# KMO_IO_M.net
KiCad netlist of a schematic drawn in EAGLE
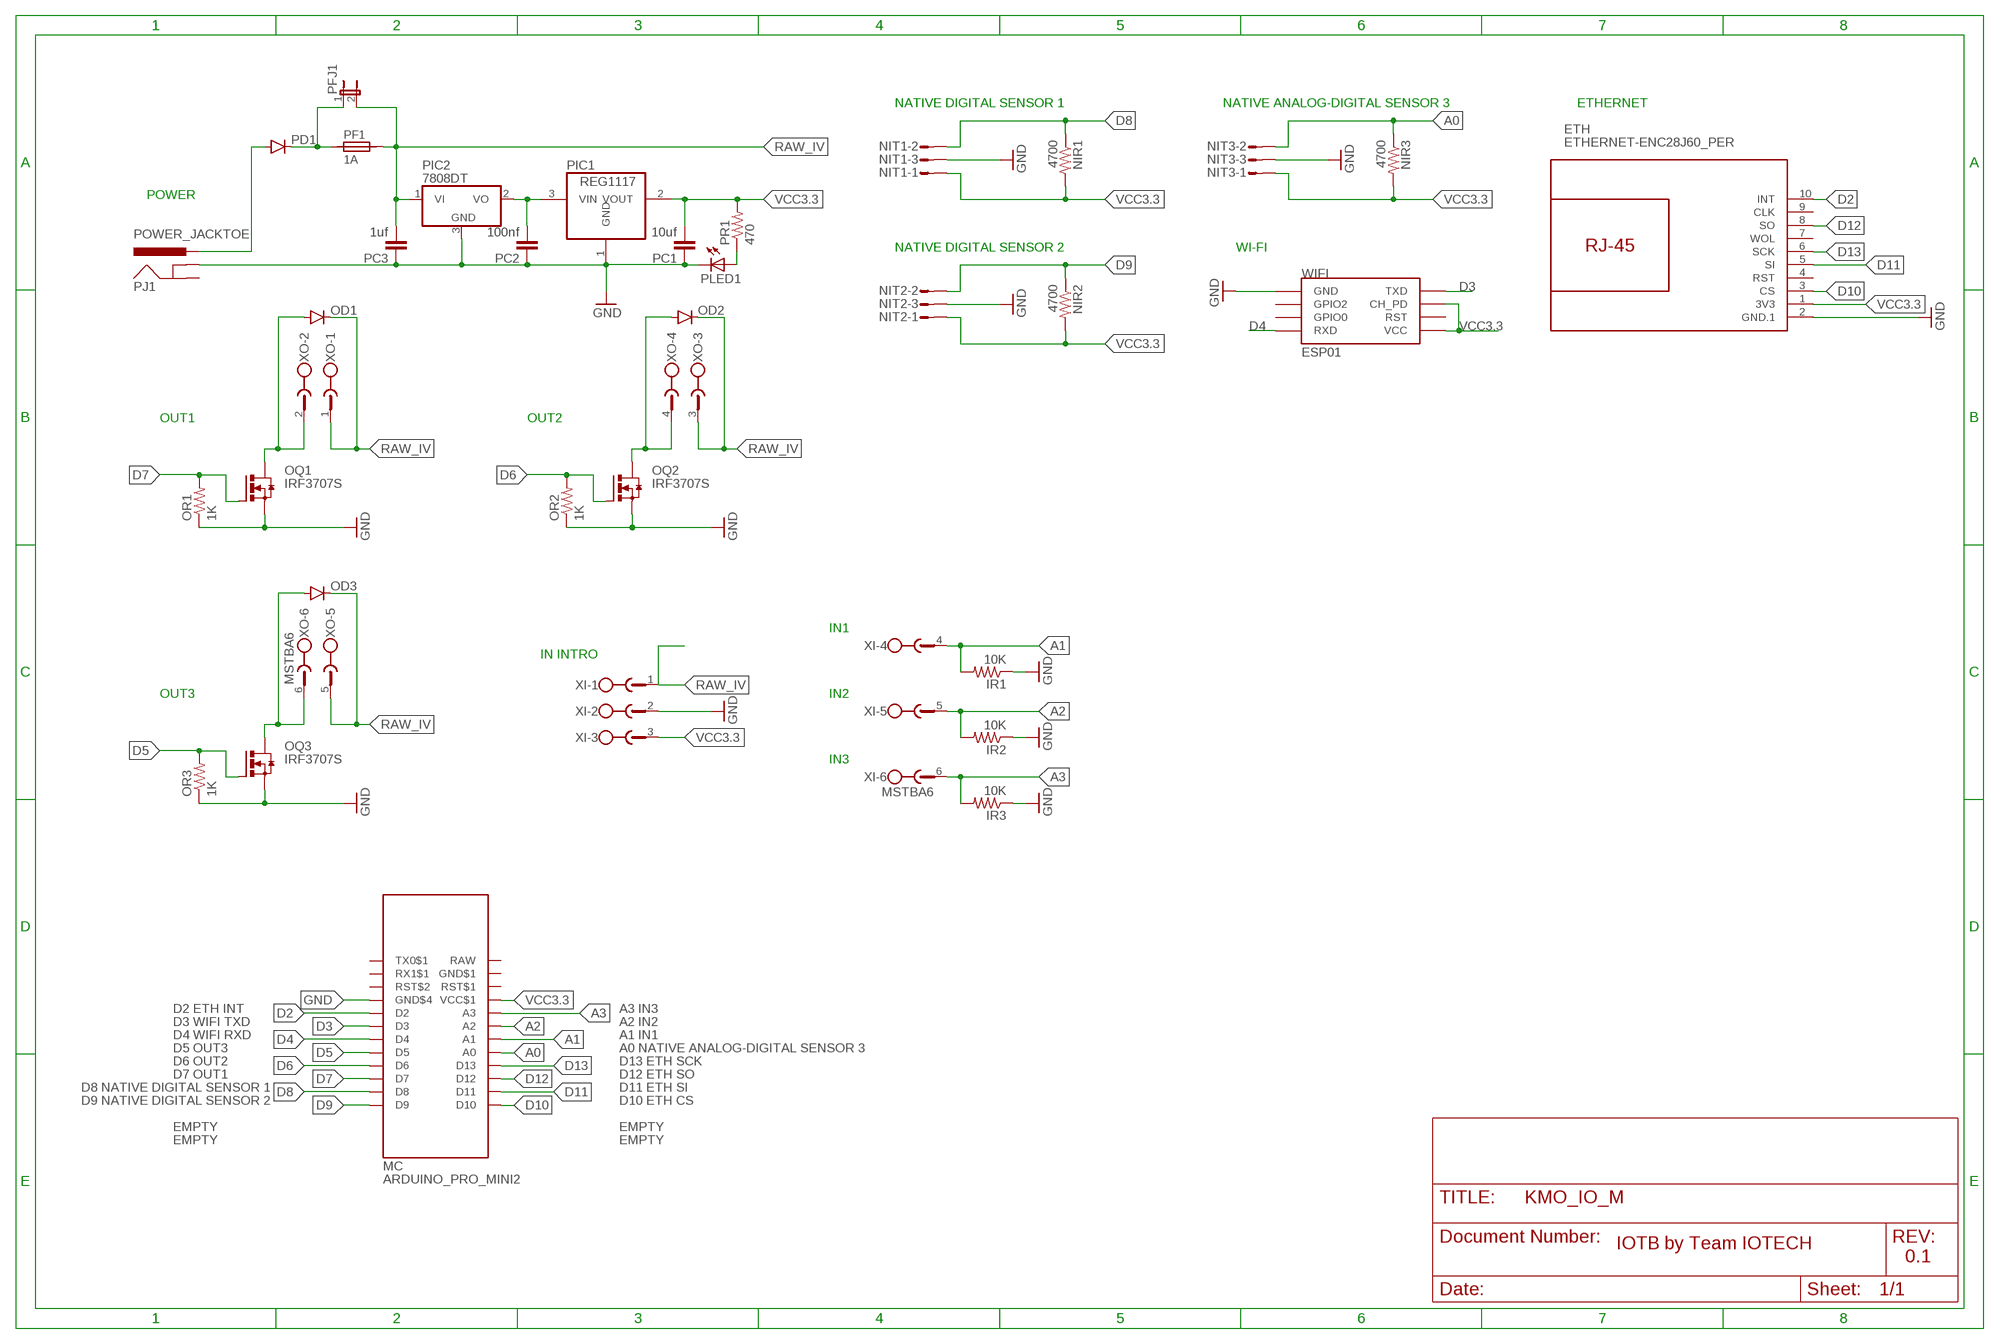
[diagram p0: schematic, sheet 1]

(export (version "E")
  (design (tool "Eeschema 10.0.6"))
  (components
    (comp (ref "ETH")
      (value "ETHERNET-ENC28J60_PER")
      (footprint "eagle-import:ETHERNET-ENC28J60_PER")
      (libsource (lib "eagle-import") (part "ETHERNET-ENC28J60_PER"))
    )
    (comp (ref "IR1")
      (value "10K")
      (footprint "eagle-import:0805")
      (libsource (lib "eagle-import") (part "RESISTOR0805-RES"))
    )
    (comp (ref "IR2")
      (value "10K")
      (footprint "eagle-import:0805")
      (libsource (lib "eagle-import") (part "RESISTOR0805-RES"))
    )
    (comp (ref "IR3")
      (value "10K")
      (footprint "eagle-import:0805")
      (libsource (lib "eagle-import") (part "RESISTOR0805-RES"))
    )
    (comp (ref "MC")
      (value "ARDUINO_PRO_MINI2")
      (footprint "eagle-import:ARDUINO_PRO_MINI2")
      (libsource (lib "eagle-import") (part "ARDUINO_PRO_MINI2"))
    )
    (comp (ref "NIR1")
      (value "4700")
      (footprint "eagle-import:0805")
      (libsource (lib "eagle-import") (part "RESISTOR0805-RES"))
    )
    (comp (ref "NIR2")
      (value "4700")
      (footprint "eagle-import:0805")
      (libsource (lib "eagle-import") (part "RESISTOR0805-RES"))
    )
    (comp (ref "NIR3")
      (value "4700")
      (footprint "eagle-import:0805")
      (libsource (lib "eagle-import") (part "RESISTOR0805-RES"))
    )
    (comp (ref "NIT1")
      (value "S03P")
      (footprint "eagle-import:S03P")
      (libsource (lib "eagle-import") (part "S03P"))
    )
    (comp (ref "NIT2")
      (value "S03P")
      (footprint "eagle-import:S03P")
      (libsource (lib "eagle-import") (part "S03P"))
    )
    (comp (ref "NIT3")
      (value "S03P")
      (footprint "eagle-import:S03P")
      (libsource (lib "eagle-import") (part "S03P"))
    )
    (comp (ref "OD1")
      (value "DIODESMA")
      (footprint "eagle-import:SMA-DIODE")
      (libsource (lib "eagle-import") (part "DIODESMA"))
    )
    (comp (ref "OD2")
      (value "DIODESMA")
      (footprint "eagle-import:SMA-DIODE")
      (libsource (lib "eagle-import") (part "DIODESMA"))
    )
    (comp (ref "OD3")
      (value "DIODESMA")
      (footprint "eagle-import:SMA-DIODE")
      (libsource (lib "eagle-import") (part "DIODESMA"))
    )
    (comp (ref "OQ1")
      (value "IRF3707S")
      (footprint "eagle-import:D2PACK")
      (libsource (lib "eagle-import") (part "IRF3704S"))
    )
    (comp (ref "OQ2")
      (value "IRF3707S")
      (footprint "eagle-import:D2PACK")
      (libsource (lib "eagle-import") (part "IRF3704S"))
    )
    (comp (ref "OQ3")
      (value "IRF3707S")
      (footprint "eagle-import:D2PACK")
      (libsource (lib "eagle-import") (part "IRF3704S"))
    )
    (comp (ref "OR1")
      (value "1K")
      (footprint "eagle-import:0805")
      (libsource (lib "eagle-import") (part "RESISTOR0805-RES"))
    )
    (comp (ref "OR2")
      (value "1K")
      (footprint "eagle-import:0805")
      (libsource (lib "eagle-import") (part "RESISTOR0805-RES"))
    )
    (comp (ref "OR3")
      (value "1K")
      (footprint "eagle-import:0805")
      (libsource (lib "eagle-import") (part "RESISTOR0805-RES"))
    )
    (comp (ref "PC1")
      (value "10uf")
      (footprint "eagle-import:0805")
      (libsource (lib "eagle-import") (part "CAP0805"))
    )
    (comp (ref "PC2")
      (value "100nf")
      (footprint "eagle-import:0805")
      (libsource (lib "eagle-import") (part "CAP0805"))
    )
    (comp (ref "PC3")
      (value "1uf")
      (footprint "eagle-import:0805")
      (libsource (lib "eagle-import") (part "CAP0805"))
    )
    (comp (ref "PD1")
      (value "DIODESMA")
      (footprint "eagle-import:SMA-DIODE")
      (libsource (lib "eagle-import") (part "DIODESMA"))
    )
    (comp (ref "PF1")
      (value "1A")
      (footprint "eagle-import:1820")
      (libsource (lib "eagle-import") (part "SIBA194600"))
    )
    (comp (ref "PFJ1")
      (value "JP1E")
      (footprint "eagle-import:JP1")
      (libsource (lib "eagle-import") (part "JP1E"))
    )
    (comp (ref "PIC1")
      (value "REG1117")
      (footprint "eagle-import:SOT223")
      (libsource (lib "eagle-import") (part "REG1117"))
    )
    (comp (ref "PIC2")
      (value "7808DT")
      (footprint "eagle-import:TO252")
      (libsource (lib "eagle-import") (part "78DT08"))
    )
    (comp (ref "PJ1")
      (value "POWER_JACKTOE")
      (footprint "eagle-import:POWER_JACK_SMD_OVERPASTE_TOE")
      (libsource (lib "eagle-import") (part "POWER_JACKTOE"))
    )
    (comp (ref "PLED1")
      (value "LEDCHIP-LED0805")
      (footprint "eagle-import:CHIP-LED0805")
      (libsource (lib "eagle-import") (part "LEDCHIP-LED0805"))
    )
    (comp (ref "PR1")
      (value "470")
      (footprint "eagle-import:0805")
      (libsource (lib "eagle-import") (part "RESISTOR0805-RES"))
    )
    (comp (ref "WIFI")
      (value "ESP01")
      (footprint "eagle-import:ESP01")
      (libsource (lib "eagle-import") (part "ESP01"))
    )
    (comp (ref "XI")
      (value "MSTBA6")
      (footprint "eagle-import:MSTBA6")
      (fields (field (name "MF") "FARNELL") (field (name "MPN") "1757284"))
      (libsource (lib "eagle-import") (part "MSTBA6"))
    )
    (comp (ref "XO")
      (value "MSTBA6")
      (footprint "eagle-import:MSTBA6")
      (fields (field (name "MF") "FARNELL") (field (name "MPN") "1757284"))
      (libsource (lib "eagle-import") (part "MSTBA6"))
    )
  )
  (nets
    (net (code "1") (name "/GND$1") (class "Default")
      (node (ref "MC") (pin "GDN$1") (pinfunction "GND$1_GDN$1") (pintype "power_in"))
    )
    (net (code "2") (name "/RAW") (class "Default")
      (node (ref "MC") (pin "RAW") (pinfunction "RAW_RAW") (pintype "power_in"))
    )
    (net (code "3") (name "A0") (class "Default")
      (node (ref "MC") (pin "A0") (pinfunction "A0_A0") (pintype "bidirectional"))
      (node (ref "NIR3") (pin "1") (pinfunction "1_1") (pintype "passive"))
      (node (ref "NIT3") (pin "2") (pinfunction "S_2") (pintype "passive"))
    )
    (net (code "4") (name "A1") (class "Default")
      (node (ref "IR1") (pin "2") (pinfunction "2_2") (pintype "passive"))
      (node (ref "MC") (pin "A1") (pinfunction "A1_A1") (pintype "bidirectional"))
      (node (ref "XI") (pin "4") (pinfunction "1_4") (pintype "passive"))
    )
    (net (code "5") (name "A2") (class "Default")
      (node (ref "IR2") (pin "2") (pinfunction "2_2") (pintype "passive"))
      (node (ref "MC") (pin "A2") (pinfunction "A2_A2") (pintype "bidirectional"))
      (node (ref "XI") (pin "5") (pinfunction "1_5") (pintype "passive"))
    )
    (net (code "6") (name "A3") (class "Default")
      (node (ref "IR3") (pin "2") (pinfunction "2_2") (pintype "passive"))
      (node (ref "MC") (pin "A3") (pinfunction "A3_A3") (pintype "bidirectional"))
      (node (ref "XI") (pin "6") (pinfunction "1_6") (pintype "passive"))
    )
    (net (code "7") (name "D2") (class "Default")
      (node (ref "ETH") (pin "10") (pinfunction "INT_10") (pintype "bidirectional"))
      (node (ref "MC") (pin "D2") (pinfunction "D2_D2") (pintype "bidirectional"))
    )
    (net (code "8") (name "D3") (class "Default")
      (node (ref "MC") (pin "D3") (pinfunction "D3_D3") (pintype "bidirectional"))
      (node (ref "WIFI") (pin "TX") (pinfunction "TXD_TX") (pintype "bidirectional"))
    )
    (net (code "9") (name "D4") (class "Default")
      (node (ref "MC") (pin "D4") (pinfunction "D4_D4") (pintype "bidirectional"))
      (node (ref "WIFI") (pin "RX") (pinfunction "RXD_RX") (pintype "bidirectional"))
    )
    (net (code "10") (name "D5") (class "Default")
      (node (ref "MC") (pin "D5") (pinfunction "D5_D5") (pintype "bidirectional"))
      (node (ref "OQ3") (pin "1") (pinfunction "G_1") (pintype "passive"))
      (node (ref "OR3") (pin "2") (pinfunction "2_2") (pintype "passive"))
    )
    (net (code "11") (name "D6") (class "Default")
      (node (ref "MC") (pin "D6") (pinfunction "D6_D6") (pintype "bidirectional"))
      (node (ref "OQ2") (pin "1") (pinfunction "G_1") (pintype "passive"))
      (node (ref "OR2") (pin "2") (pinfunction "2_2") (pintype "passive"))
    )
    (net (code "12") (name "D7") (class "Default")
      (node (ref "MC") (pin "D7") (pinfunction "D7_D7") (pintype "bidirectional"))
      (node (ref "OQ1") (pin "1") (pinfunction "G_1") (pintype "passive"))
      (node (ref "OR1") (pin "2") (pinfunction "2_2") (pintype "passive"))
    )
    (net (code "13") (name "D8") (class "Default")
      (node (ref "MC") (pin "D8") (pinfunction "D8_D8") (pintype "bidirectional"))
      (node (ref "NIR1") (pin "1") (pinfunction "1_1") (pintype "passive"))
      (node (ref "NIT1") (pin "2") (pinfunction "S_2") (pintype "passive"))
    )
    (net (code "14") (name "D9") (class "Default")
      (node (ref "MC") (pin "D9") (pinfunction "D9_D9") (pintype "bidirectional"))
      (node (ref "NIR2") (pin "1") (pinfunction "1_1") (pintype "passive"))
      (node (ref "NIT2") (pin "2") (pinfunction "S_2") (pintype "passive"))
    )
    (net (code "15") (name "D10") (class "Default")
      (node (ref "ETH") (pin "3") (pinfunction "CS_3") (pintype "bidirectional"))
      (node (ref "MC") (pin "D10") (pinfunction "D10_D10") (pintype "bidirectional"))
    )
    (net (code "16") (name "D11") (class "Default")
      (node (ref "ETH") (pin "5") (pinfunction "SI_5") (pintype "bidirectional"))
      (node (ref "MC") (pin "D11") (pinfunction "D11_D11") (pintype "bidirectional"))
    )
    (net (code "17") (name "D12") (class "Default")
      (node (ref "ETH") (pin "8") (pinfunction "SO_8") (pintype "bidirectional"))
      (node (ref "MC") (pin "D12") (pinfunction "D12_D12") (pintype "bidirectional"))
    )
    (net (code "18") (name "D13") (class "Default")
      (node (ref "ETH") (pin "6") (pinfunction "SCK_6") (pintype "bidirectional"))
      (node (ref "MC") (pin "D13") (pinfunction "D13_D13") (pintype "bidirectional"))
    )
    (net (code "19") (name "GND") (class "Default")
      (node (ref "ETH") (pin "2") (pinfunction "GND.1_2") (pintype "power_in"))
      (node (ref "IR1") (pin "1") (pinfunction "1_1") (pintype "passive"))
      (node (ref "IR2") (pin "1") (pinfunction "1_1") (pintype "passive"))
      (node (ref "IR3") (pin "1") (pinfunction "1_1") (pintype "passive"))
      (node (ref "MC") (pin "GND$4") (pinfunction "GND$4_GND$4") (pintype "power_in"))
      (node (ref "NIT1") (pin "3") (pinfunction "S_3") (pintype "passive"))
      (node (ref "NIT2") (pin "3") (pinfunction "S_3") (pintype "passive"))
      (node (ref "NIT3") (pin "3") (pinfunction "S_3") (pintype "passive"))
      (node (ref "OQ1") (pin "3") (pinfunction "S_3") (pintype "passive"))
      (node (ref "OQ2") (pin "3") (pinfunction "S_3") (pintype "passive"))
      (node (ref "OQ3") (pin "3") (pinfunction "S_3") (pintype "passive"))
      (node (ref "OR1") (pin "1") (pinfunction "1_1") (pintype "passive"))
      (node (ref "OR2") (pin "1") (pinfunction "1_1") (pintype "passive"))
      (node (ref "OR3") (pin "1") (pinfunction "1_1") (pintype "passive"))
      (node (ref "PC1") (pin "1") (pinfunction "1_1") (pintype "passive"))
      (node (ref "PC2") (pin "1") (pinfunction "1_1") (pintype "passive"))
      (node (ref "PC3") (pin "1") (pinfunction "1_1") (pintype "passive"))
      (node (ref "PIC1") (pin "1") (pinfunction "GND_1") (pintype "power_in"))
      (node (ref "PIC2") (pin "3") (pinfunction "GND_3") (pintype "passive"))
      (node (ref "PJ1") (pin "GND") (pinfunction "GNDBREAK_GND") (pintype "bidirectional"))
      (node (ref "PLED1") (pin "C") (pinfunction "C_C") (pintype "passive"))
      (node (ref "WIFI") (pin "GND") (pinfunction "GND_GND") (pintype "bidirectional"))
      (node (ref "XI") (pin "2") (pinfunction "1_2") (pintype "passive"))
    )
    (net (code "20") (name "Net-(OQ1-D)") (class "Default")
      (node (ref "OD1") (pin "A") (pinfunction "A_A") (pintype "passive"))
      (node (ref "OQ1") (pin "2") (pinfunction "D_2") (pintype "passive"))
      (node (ref "XO") (pin "2") (pinfunction "1_2") (pintype "passive"))
    )
    (net (code "21") (name "Net-(OQ2-D)") (class "Default")
      (node (ref "OD2") (pin "A") (pinfunction "A_A") (pintype "passive"))
      (node (ref "OQ2") (pin "2") (pinfunction "D_2") (pintype "passive"))
      (node (ref "XO") (pin "4") (pinfunction "1_4") (pintype "passive"))
    )
    (net (code "22") (name "Net-(OQ3-D)") (class "Default")
      (node (ref "OD3") (pin "A") (pinfunction "A_A") (pintype "passive"))
      (node (ref "OQ3") (pin "2") (pinfunction "D_2") (pintype "passive"))
      (node (ref "XO") (pin "6") (pinfunction "1_6") (pintype "passive"))
    )
    (net (code "23") (name "Net-(PD1-PadC)") (class "Default")
      (node (ref "PD1") (pin "C") (pinfunction "C_C") (pintype "passive"))
      (node (ref "PF1") (pin "1") (pinfunction "1_1") (pintype "passive"))
      (node (ref "PFJ1") (pin "1") (pinfunction "1_1") (pintype "passive"))
    )
    (net (code "24") (name "Net-(PIC1-VIN)") (class "Default")
      (node (ref "PC2") (pin "2") (pinfunction "2_2") (pintype "passive"))
      (node (ref "PIC1") (pin "3") (pinfunction "VIN_3") (pintype "input"))
      (node (ref "PIC2") (pin "2") (pinfunction "VO_2") (pintype "passive"))
    )
    (net (code "25") (name "Net-(PJ1-PWR)") (class "Default")
      (node (ref "PD1") (pin "A") (pinfunction "A_A") (pintype "passive"))
      (node (ref "PJ1") (pin "VIN0") (pinfunction "PWR_VIN0") (pintype "bidirectional"))
    )
    (net (code "26") (name "Net-(PLED1-PadA)") (class "Default")
      (node (ref "PLED1") (pin "A") (pinfunction "A_A") (pintype "passive"))
      (node (ref "PR1") (pin "1") (pinfunction "1_1") (pintype "passive"))
    )
    (net (code "27") (name "RAW_IV") (class "Default")
      (node (ref "OD1") (pin "C") (pinfunction "C_C") (pintype "passive"))
      (node (ref "OD2") (pin "C") (pinfunction "C_C") (pintype "passive"))
      (node (ref "OD3") (pin "C") (pinfunction "C_C") (pintype "passive"))
      (node (ref "PC3") (pin "2") (pinfunction "2_2") (pintype "passive"))
      (node (ref "PF1") (pin "2") (pinfunction "2_2") (pintype "passive"))
      (node (ref "PFJ1") (pin "2") (pinfunction "2_2") (pintype "passive"))
      (node (ref "PIC2") (pin "1") (pinfunction "VI_1") (pintype "input"))
      (node (ref "XI") (pin "1") (pinfunction "1_1") (pintype "passive"))
      (node (ref "XO") (pin "1") (pinfunction "1_1") (pintype "passive"))
      (node (ref "XO") (pin "3") (pinfunction "1_3") (pintype "passive"))
      (node (ref "XO") (pin "5") (pinfunction "1_5") (pintype "passive"))
    )
    (net (code "28") (name "VCC3.3") (class "Default")
      (node (ref "ETH") (pin "1") (pinfunction "3V3_1") (pintype "power_in"))
      (node (ref "MC") (pin "VCC$1") (pinfunction "VCC$1_VCC$1") (pintype "power_in"))
      (node (ref "NIR1") (pin "2") (pinfunction "2_2") (pintype "passive"))
      (node (ref "NIR2") (pin "2") (pinfunction "2_2") (pintype "passive"))
      (node (ref "NIR3") (pin "2") (pinfunction "2_2") (pintype "passive"))
      (node (ref "NIT1") (pin "1") (pinfunction "S_1") (pintype "passive"))
      (node (ref "NIT2") (pin "1") (pinfunction "S_1") (pintype "passive"))
      (node (ref "NIT3") (pin "1") (pinfunction "S_1") (pintype "passive"))
      (node (ref "PC1") (pin "2") (pinfunction "2_2") (pintype "passive"))
      (node (ref "PIC1") (pin "2") (pinfunction "VOUT_2") (pintype "output"))
      (node (ref "PR1") (pin "2") (pinfunction "2_2") (pintype "passive"))
      (node (ref "WIFI") (pin "CH_PD") (pinfunction "CH_PD_CH_PD") (pintype "bidirectional"))
      (node (ref "WIFI") (pin "VCC") (pinfunction "VCC_VCC") (pintype "bidirectional"))
      (node (ref "XI") (pin "3") (pinfunction "1_3") (pintype "passive"))
    )
    (net (code "29") (name "unconnected-(ETH-CLK-Pad9)") (class "Default")
      (node (ref "ETH") (pin "9") (pinfunction "CLK_9") (pintype "bidirectional"))
    )
    (net (code "30") (name "unconnected-(ETH-RST-Pad4)") (class "Default")
      (node (ref "ETH") (pin "4") (pinfunction "RST_4") (pintype "bidirectional"))
    )
    (net (code "31") (name "unconnected-(ETH-WOL-Pad7)") (class "Default")
      (node (ref "ETH") (pin "7") (pinfunction "WOL_7") (pintype "bidirectional"))
    )
    (net (code "32") (name "unconnected-(MC-PadRST$1)") (class "Default")
      (node (ref "MC") (pin "RST$1") (pinfunction "RST$1_RST$1") (pintype "input"))
    )
    (net (code "33") (name "unconnected-(MC-PadRST$2)") (class "Default")
      (node (ref "MC") (pin "RST$2") (pinfunction "RST$2_RST$2") (pintype "input"))
    )
    (net (code "34") (name "unconnected-(MC-PadRX1$1)") (class "Default")
      (node (ref "MC") (pin "RX1$1") (pinfunction "RX1$1_RX1$1") (pintype "bidirectional"))
    )
    (net (code "35") (name "unconnected-(MC-PadTX0$1)") (class "Default")
      (node (ref "MC") (pin "TX0$1") (pinfunction "TX0$1_TX0$1") (pintype "bidirectional"))
    )
    (net (code "36") (name "unconnected-(PJ1-GND-PadP$4)") (class "Default")
      (node (ref "PJ1") (pin "P$4") (pinfunction "GND_P$4") (pintype "bidirectional"))
    )
    (net (code "37") (name "unconnected-(WIFI-PadGPIO0)") (class "Default")
      (node (ref "WIFI") (pin "GPIO0") (pinfunction "GPIO0_GPIO0") (pintype "bidirectional"))
    )
    (net (code "38") (name "unconnected-(WIFI-PadGPIO2)") (class "Default")
      (node (ref "WIFI") (pin "GPIO2") (pinfunction "GPIO2_GPIO2") (pintype "bidirectional"))
    )
    (net (code "39") (name "unconnected-(WIFI-PadRST)") (class "Default")
      (node (ref "WIFI") (pin "RST") (pinfunction "RST_RST") (pintype "bidirectional"))
    )
  )
)
